# LED_Sticks.net
KiCad netlist of a schematic drawn in EAGLE
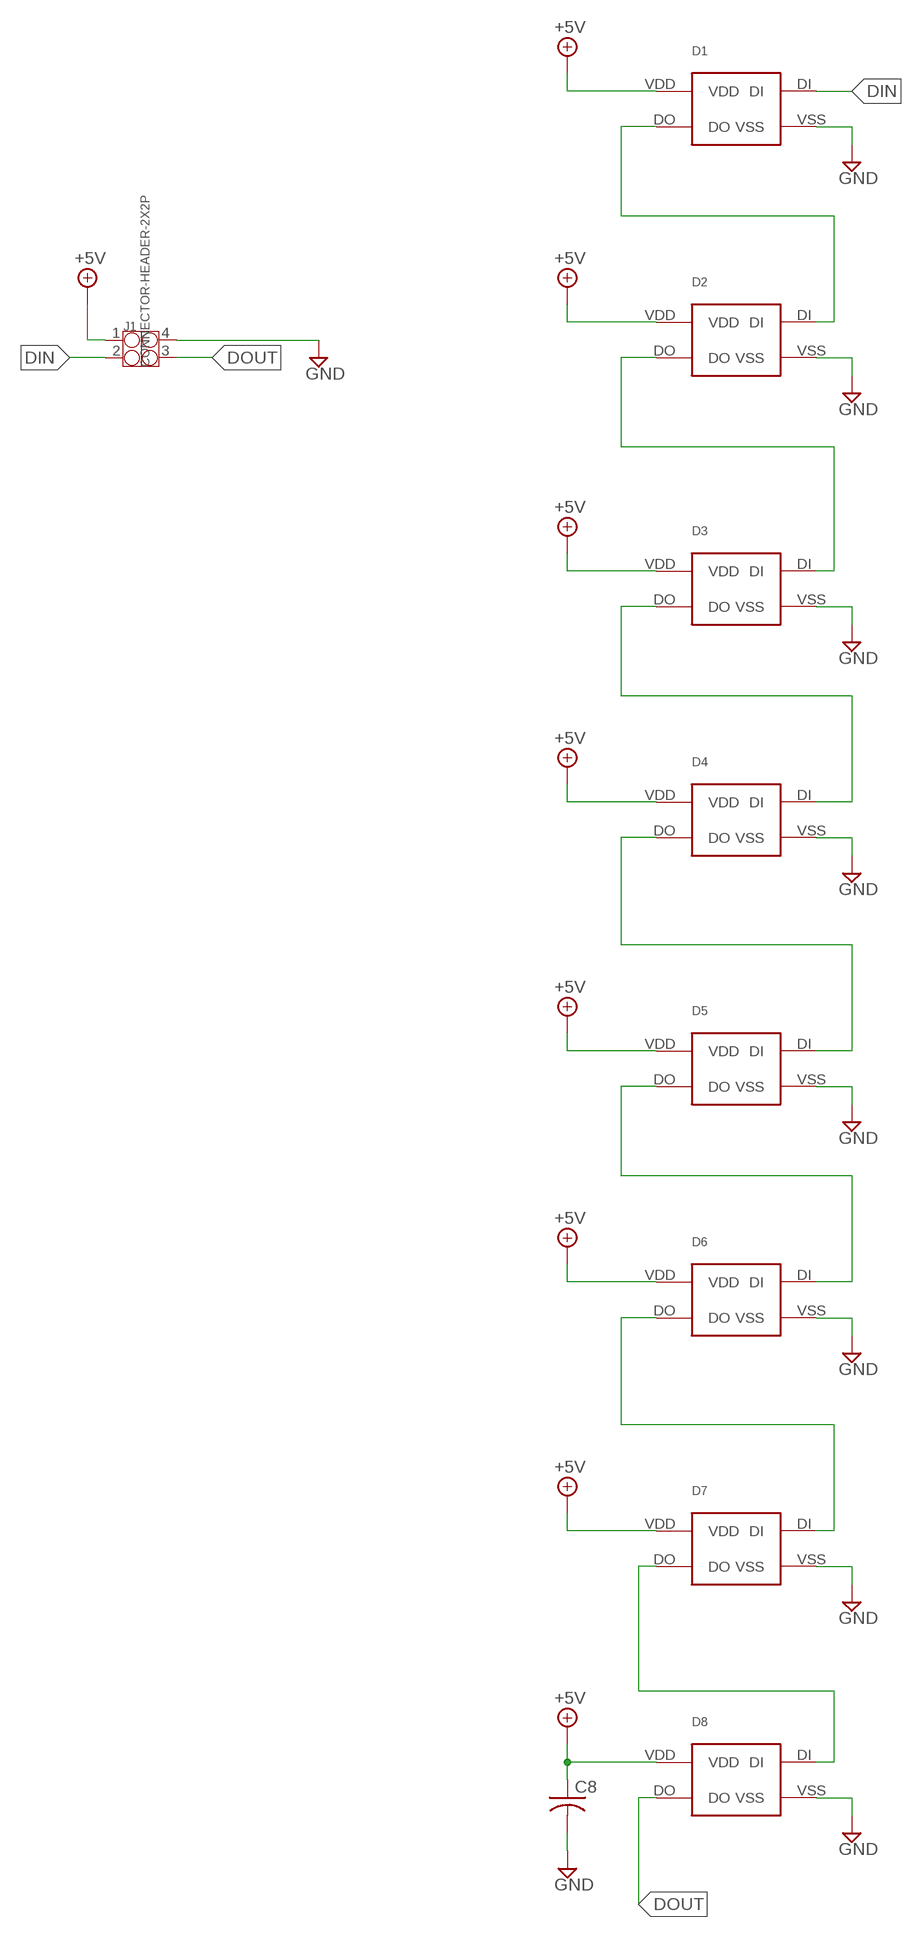
[diagram p0: schematic, sheet 1]

(export (version "E")
  (design (tool "Eeschema 10.0.6"))
  (components
    (comp (ref "C8")
      (value "C-USC0603K")
      (footprint "eagle-import:C0603K")
      (libsource (lib "eagle-import") (part "C-USC0603K"))
    )
    (comp (ref "D1")
      (value "WS2812B")
      (footprint "eagle-import:WS2812B")
      (libsource (lib "eagle-import") (part "WS2812B"))
    )
    (comp (ref "D2")
      (value "WS2812B")
      (footprint "eagle-import:WS2812B")
      (libsource (lib "eagle-import") (part "WS2812B"))
    )
    (comp (ref "D3")
      (value "WS2812B")
      (footprint "eagle-import:WS2812B")
      (libsource (lib "eagle-import") (part "WS2812B"))
    )
    (comp (ref "D4")
      (value "WS2812B")
      (footprint "eagle-import:WS2812B")
      (libsource (lib "eagle-import") (part "WS2812B"))
    )
    (comp (ref "D5")
      (value "WS2812B")
      (footprint "eagle-import:WS2812B")
      (libsource (lib "eagle-import") (part "WS2812B"))
    )
    (comp (ref "D6")
      (value "WS2812B")
      (footprint "eagle-import:WS2812B")
      (libsource (lib "eagle-import") (part "WS2812B"))
    )
    (comp (ref "D7")
      (value "WS2812B")
      (footprint "eagle-import:WS2812B")
      (libsource (lib "eagle-import") (part "WS2812B"))
    )
    (comp (ref "D8")
      (value "WS2812B")
      (footprint "eagle-import:WS2812B")
      (libsource (lib "eagle-import") (part "WS2812B"))
    )
    (comp (ref "J1")
      (value "CONNECTOR-HEADER-2X2P")
      (footprint "eagle-import:2X2P-2.54")
      (libsource (lib "eagle-import") (part "CONNECTOR-HEADER-2X2P"))
    )
  )
  (nets
    (net (code "1") (name "+5V") (class "Default")
      (node (ref "C8") (pin "1") (pinfunction "1_1") (pintype "passive"))
      (node (ref "D1") (pin "VDD") (pinfunction "VDD_VDD") (pintype "bidirectional"))
      (node (ref "D2") (pin "VDD") (pinfunction "VDD_VDD") (pintype "bidirectional"))
      (node (ref "D3") (pin "VDD") (pinfunction "VDD_VDD") (pintype "bidirectional"))
      (node (ref "D4") (pin "VDD") (pinfunction "VDD_VDD") (pintype "bidirectional"))
      (node (ref "D5") (pin "VDD") (pinfunction "VDD_VDD") (pintype "bidirectional"))
      (node (ref "D6") (pin "VDD") (pinfunction "VDD_VDD") (pintype "bidirectional"))
      (node (ref "D7") (pin "VDD") (pinfunction "VDD_VDD") (pintype "bidirectional"))
      (node (ref "D8") (pin "VDD") (pinfunction "VDD_VDD") (pintype "bidirectional"))
      (node (ref "J1") (pin "1") (pinfunction "1_1") (pintype "bidirectional"))
    )
    (net (code "2") (name "DIN") (class "Default")
      (node (ref "D1") (pin "DI") (pinfunction "DI_DI") (pintype "bidirectional"))
      (node (ref "J1") (pin "2") (pinfunction "2_2") (pintype "bidirectional"))
    )
    (net (code "3") (name "DOUT") (class "Default")
      (node (ref "D8") (pin "DO") (pinfunction "DO_DO") (pintype "bidirectional"))
      (node (ref "J1") (pin "3") (pinfunction "3_3") (pintype "bidirectional"))
    )
    (net (code "4") (name "GND") (class "Default")
      (node (ref "C8") (pin "2") (pinfunction "2_2") (pintype "passive"))
      (node (ref "D1") (pin "VSS") (pinfunction "VSS_VSS") (pintype "bidirectional"))
      (node (ref "D2") (pin "VSS") (pinfunction "VSS_VSS") (pintype "bidirectional"))
      (node (ref "D3") (pin "VSS") (pinfunction "VSS_VSS") (pintype "bidirectional"))
      (node (ref "D4") (pin "VSS") (pinfunction "VSS_VSS") (pintype "bidirectional"))
      (node (ref "D5") (pin "VSS") (pinfunction "VSS_VSS") (pintype "bidirectional"))
      (node (ref "D6") (pin "VSS") (pinfunction "VSS_VSS") (pintype "bidirectional"))
      (node (ref "D7") (pin "VSS") (pinfunction "VSS_VSS") (pintype "bidirectional"))
      (node (ref "D8") (pin "VSS") (pinfunction "VSS_VSS") (pintype "bidirectional"))
      (node (ref "J1") (pin "4") (pinfunction "4_4") (pintype "bidirectional"))
    )
    (net (code "5") (name "Net-(D1-PadDO)") (class "Default")
      (node (ref "D1") (pin "DO") (pinfunction "DO_DO") (pintype "bidirectional"))
      (node (ref "D2") (pin "DI") (pinfunction "DI_DI") (pintype "bidirectional"))
    )
    (net (code "6") (name "Net-(D2-PadDO)") (class "Default")
      (node (ref "D2") (pin "DO") (pinfunction "DO_DO") (pintype "bidirectional"))
      (node (ref "D3") (pin "DI") (pinfunction "DI_DI") (pintype "bidirectional"))
    )
    (net (code "7") (name "Net-(D3-PadDO)") (class "Default")
      (node (ref "D3") (pin "DO") (pinfunction "DO_DO") (pintype "bidirectional"))
      (node (ref "D4") (pin "DI") (pinfunction "DI_DI") (pintype "bidirectional"))
    )
    (net (code "8") (name "Net-(D4-PadDO)") (class "Default")
      (node (ref "D4") (pin "DO") (pinfunction "DO_DO") (pintype "bidirectional"))
      (node (ref "D5") (pin "DI") (pinfunction "DI_DI") (pintype "bidirectional"))
    )
    (net (code "9") (name "Net-(D5-PadDO)") (class "Default")
      (node (ref "D5") (pin "DO") (pinfunction "DO_DO") (pintype "bidirectional"))
      (node (ref "D6") (pin "DI") (pinfunction "DI_DI") (pintype "bidirectional"))
    )
    (net (code "10") (name "Net-(D6-PadDO)") (class "Default")
      (node (ref "D6") (pin "DO") (pinfunction "DO_DO") (pintype "bidirectional"))
      (node (ref "D7") (pin "DI") (pinfunction "DI_DI") (pintype "bidirectional"))
    )
    (net (code "11") (name "Net-(D7-PadDO)") (class "Default")
      (node (ref "D7") (pin "DO") (pinfunction "DO_DO") (pintype "bidirectional"))
      (node (ref "D8") (pin "DI") (pinfunction "DI_DI") (pintype "bidirectional"))
    )
  )
)
